# 02_M283.net
KiCad netlist of a schematic drawn in Altium Designer
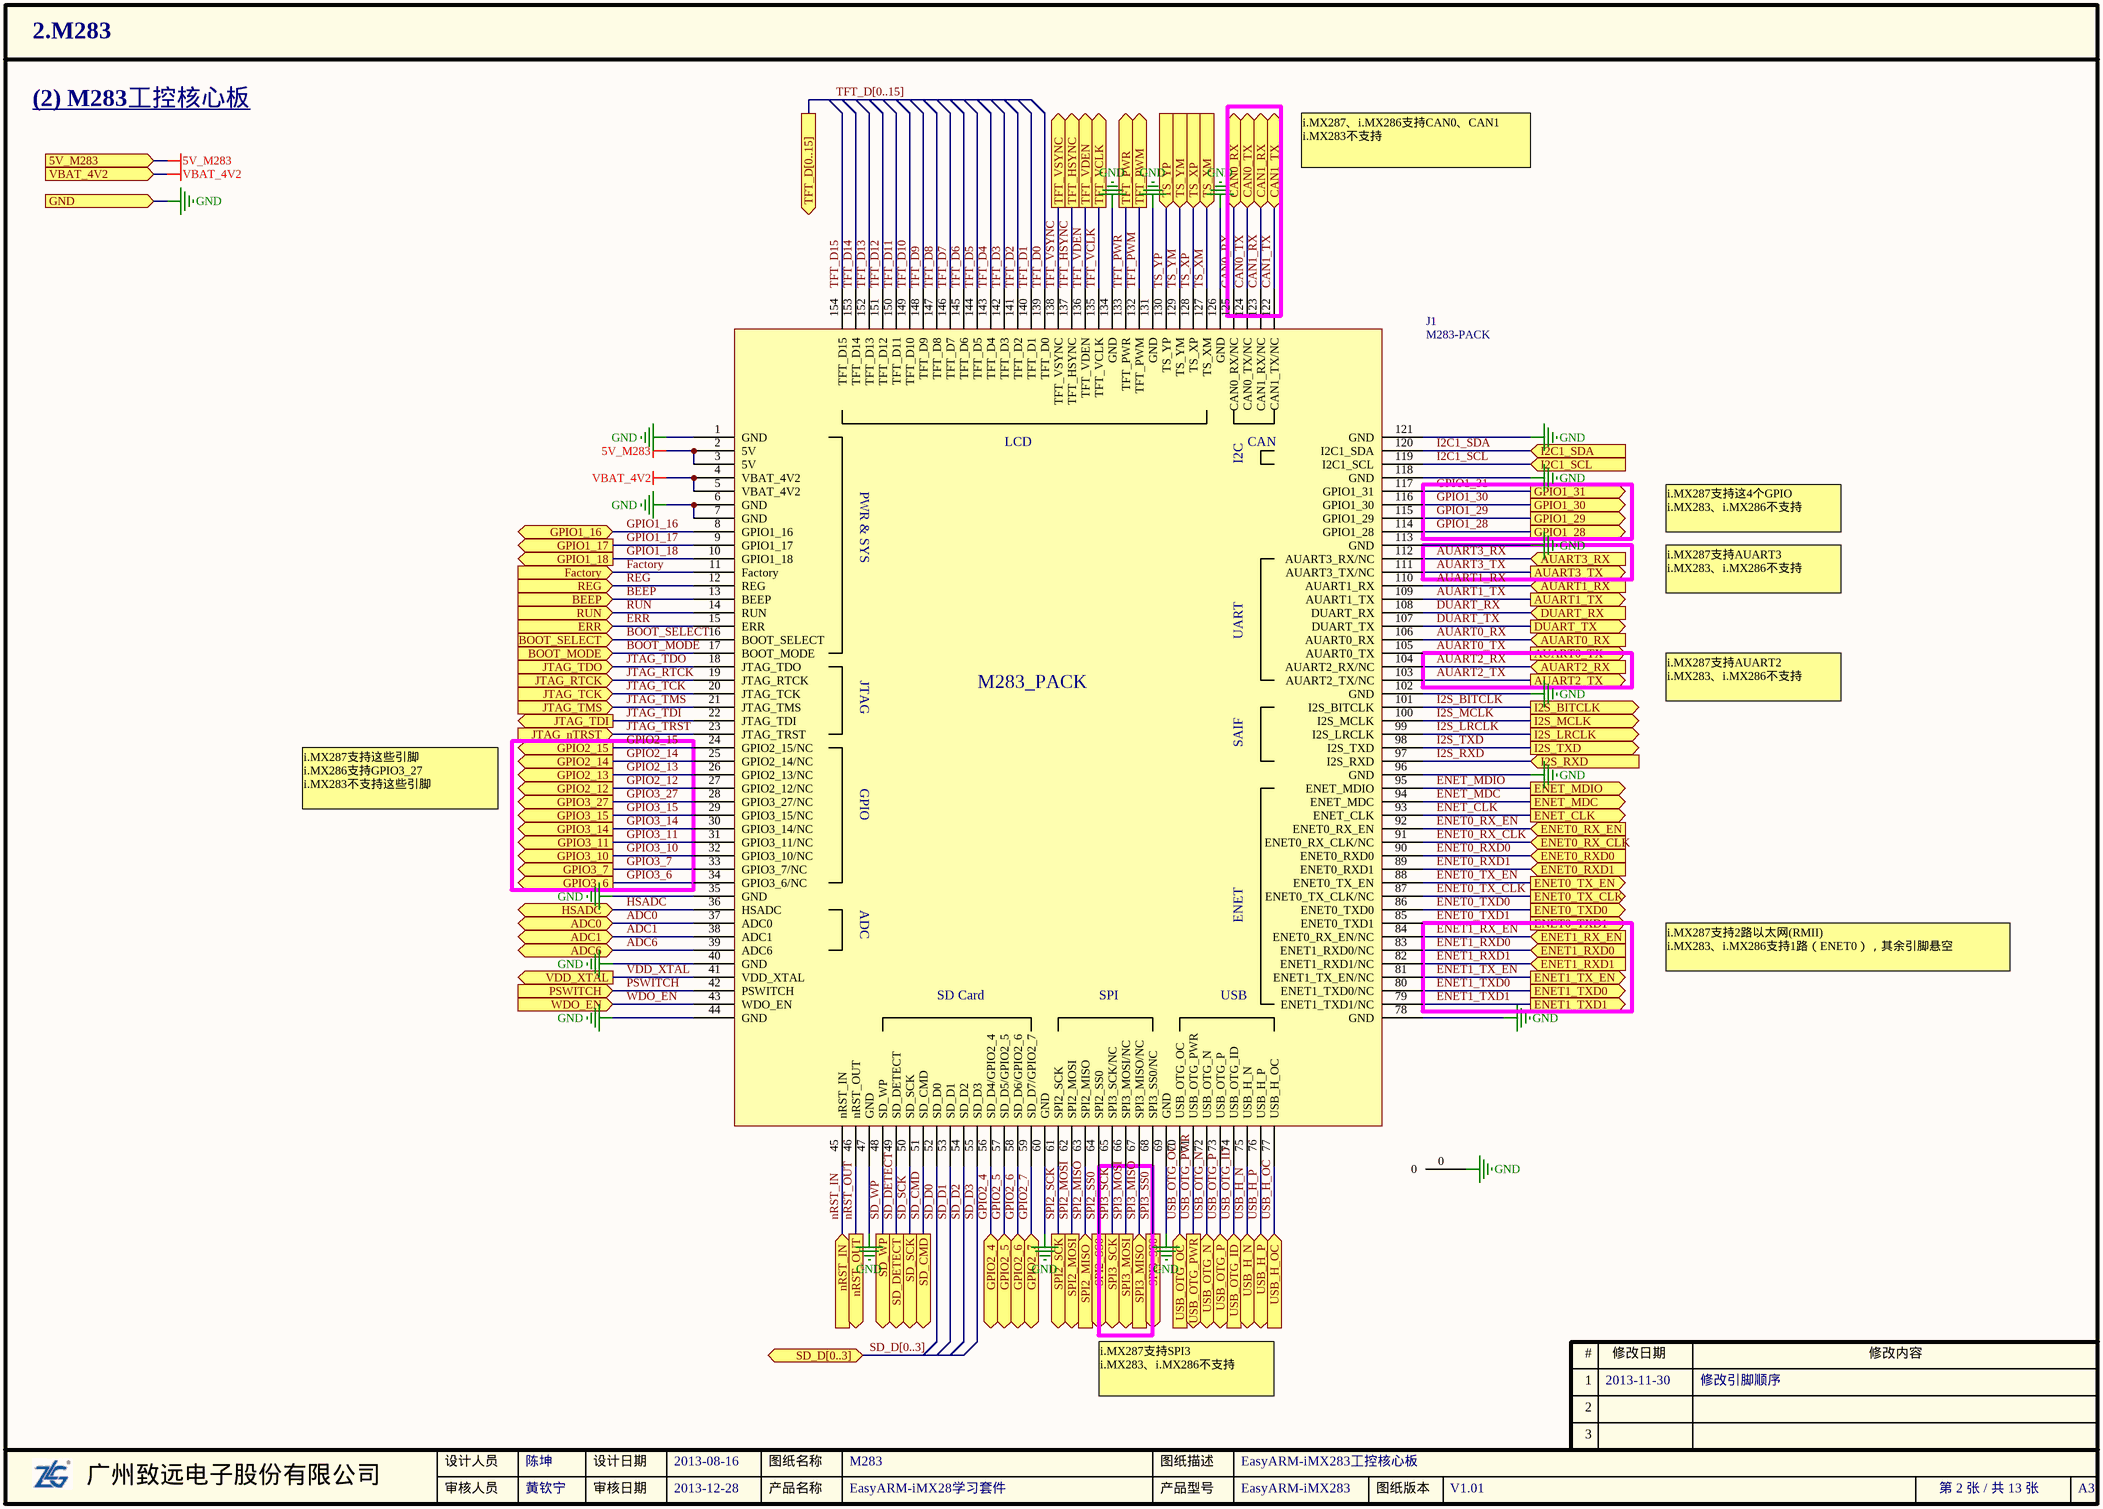
[diagram p0: 02. M283.SchDoc]

(export (version "E")
  (design (tool "Eeschema 10.0.6"))
  (components
    (comp (ref "J1")
      (value "M283-PACK")
      (footprint "M283-154")
      (description "M283")
      (libsource (lib "M283") (part "M283-PACK"))
    )
  )
  (nets
    (net (code "1") (name "/ADC0") (class "Default")
      (node (ref "J1") (pin "37") (pinfunction "ADC0_37") (pintype "passive"))
    )
    (net (code "2") (name "/ADC1") (class "Default")
      (node (ref "J1") (pin "38") (pinfunction "ADC1_38") (pintype "passive"))
    )
    (net (code "3") (name "/ADC6") (class "Default")
      (node (ref "J1") (pin "39") (pinfunction "ADC6_39") (pintype "passive"))
    )
    (net (code "4") (name "/AUART0_RX") (class "Default")
      (node (ref "J1") (pin "106") (pinfunction "AUART0_RX_106") (pintype "passive"))
    )
    (net (code "5") (name "/AUART0_TX") (class "Default")
      (node (ref "J1") (pin "105") (pinfunction "AUART0_TX_105") (pintype "passive"))
    )
    (net (code "6") (name "/AUART1_RX") (class "Default")
      (node (ref "J1") (pin "110") (pinfunction "AUART1_RX_110") (pintype "passive"))
    )
    (net (code "7") (name "/AUART1_TX") (class "Default")
      (node (ref "J1") (pin "109") (pinfunction "AUART1_TX_109") (pintype "passive"))
    )
    (net (code "8") (name "/AUART2_RX") (class "Default")
      (node (ref "J1") (pin "104") (pinfunction "AUART2_RX/NC_104") (pintype "passive"))
    )
    (net (code "9") (name "/AUART2_TX") (class "Default")
      (node (ref "J1") (pin "103") (pinfunction "AUART2_TX/NC_103") (pintype "passive"))
    )
    (net (code "10") (name "/AUART3_RX") (class "Default")
      (node (ref "J1") (pin "112") (pinfunction "AUART3_RX/NC_112") (pintype "passive"))
    )
    (net (code "11") (name "/AUART3_TX") (class "Default")
      (node (ref "J1") (pin "111") (pinfunction "AUART3_TX/NC_111") (pintype "passive"))
    )
    (net (code "12") (name "/BEEP") (class "Default")
      (node (ref "J1") (pin "13") (pinfunction "BEEP_13") (pintype "passive"))
    )
    (net (code "13") (name "/BOOT_MODE") (class "Default")
      (node (ref "J1") (pin "17") (pinfunction "BOOT_MODE_17") (pintype "passive"))
    )
    (net (code "14") (name "/BOOT_SELECT") (class "Default")
      (node (ref "J1") (pin "16") (pinfunction "BOOT_SELECT_16") (pintype "passive"))
    )
    (net (code "15") (name "/CAN0_RX") (class "Default")
      (node (ref "J1") (pin "125") (pinfunction "CAN0_RX/NC_125") (pintype "passive"))
    )
    (net (code "16") (name "/CAN0_TX") (class "Default")
      (node (ref "J1") (pin "124") (pinfunction "CAN0_TX/NC_124") (pintype "passive"))
    )
    (net (code "17") (name "/CAN1_RX") (class "Default")
      (node (ref "J1") (pin "123") (pinfunction "CAN1_RX/NC_123") (pintype "passive"))
    )
    (net (code "18") (name "/CAN1_TX") (class "Default")
      (node (ref "J1") (pin "122") (pinfunction "CAN1_TX/NC_122") (pintype "passive"))
    )
    (net (code "19") (name "/DUART_RX") (class "Default")
      (node (ref "J1") (pin "108") (pinfunction "DUART_RX_108") (pintype "passive"))
    )
    (net (code "20") (name "/DUART_TX") (class "Default")
      (node (ref "J1") (pin "107") (pinfunction "DUART_TX_107") (pintype "passive"))
    )
    (net (code "21") (name "/ENET0_RXD0") (class "Default")
      (node (ref "J1") (pin "90") (pinfunction "ENET0_RXD0_90") (pintype "passive"))
    )
    (net (code "22") (name "/ENET0_RXD1") (class "Default")
      (node (ref "J1") (pin "89") (pinfunction "ENET0_RXD1_89") (pintype "passive"))
    )
    (net (code "23") (name "/ENET0_RX_CLK") (class "Default")
      (node (ref "J1") (pin "91") (pinfunction "ENET0_RX_CLK/NC_91") (pintype "passive"))
    )
    (net (code "24") (name "/ENET0_RX_EN") (class "Default")
      (node (ref "J1") (pin "92") (pinfunction "ENET0_RX_EN_92") (pintype "passive"))
    )
    (net (code "25") (name "/ENET0_TXD0") (class "Default")
      (node (ref "J1") (pin "86") (pinfunction "ENET0_TXD0_86") (pintype "passive"))
    )
    (net (code "26") (name "/ENET0_TXD1") (class "Default")
      (node (ref "J1") (pin "85") (pinfunction "ENET0_TXD1_85") (pintype "passive"))
    )
    (net (code "27") (name "/ENET0_TX_CLK") (class "Default")
      (node (ref "J1") (pin "87") (pinfunction "ENET0_TX_CLK/NC_87") (pintype "passive"))
    )
    (net (code "28") (name "/ENET0_TX_EN") (class "Default")
      (node (ref "J1") (pin "88") (pinfunction "ENET0_TX_EN_88") (pintype "passive"))
    )
    (net (code "29") (name "/ENET1_RXD0") (class "Default")
      (node (ref "J1") (pin "83") (pinfunction "ENET1_RXD0/NC_83") (pintype "passive"))
    )
    (net (code "30") (name "/ENET1_RXD1") (class "Default")
      (node (ref "J1") (pin "82") (pinfunction "ENET1_RXD1/NC_82") (pintype "passive"))
    )
    (net (code "31") (name "/ENET1_RX_EN") (class "Default")
      (node (ref "J1") (pin "84") (pinfunction "ENET0_RX_EN/NC_84") (pintype "passive"))
    )
    (net (code "32") (name "/ENET1_TXD0") (class "Default")
      (node (ref "J1") (pin "80") (pinfunction "ENET1_TXD0/NC_80") (pintype "passive"))
    )
    (net (code "33") (name "/ENET1_TXD1") (class "Default")
      (node (ref "J1") (pin "79") (pinfunction "ENET1_TXD1/NC_79") (pintype "passive"))
    )
    (net (code "34") (name "/ENET1_TX_EN") (class "Default")
      (node (ref "J1") (pin "81") (pinfunction "ENET1_TX_EN/NC_81") (pintype "passive"))
    )
    (net (code "35") (name "/ENET_CLK") (class "Default")
      (node (ref "J1") (pin "93") (pinfunction "ENET_CLK_93") (pintype "passive"))
    )
    (net (code "36") (name "/ENET_MDC") (class "Default")
      (node (ref "J1") (pin "94") (pinfunction "ENET_MDC_94") (pintype "passive"))
    )
    (net (code "37") (name "/ENET_MDIO") (class "Default")
      (node (ref "J1") (pin "95") (pinfunction "ENET_MDIO_95") (pintype "passive"))
    )
    (net (code "38") (name "/ERR") (class "Default")
      (node (ref "J1") (pin "15") (pinfunction "ERR_15") (pintype "passive"))
    )
    (net (code "39") (name "/Factory") (class "Default")
      (node (ref "J1") (pin "11") (pinfunction "Factory_11") (pintype "passive"))
    )
    (net (code "40") (name "/GPIO1_16") (class "Default")
      (node (ref "J1") (pin "8") (pinfunction "GPIO1_16_8") (pintype "passive"))
    )
    (net (code "41") (name "/GPIO1_17") (class "Default")
      (node (ref "J1") (pin "9") (pinfunction "GPIO1_17_9") (pintype "passive"))
    )
    (net (code "42") (name "/GPIO1_18") (class "Default")
      (node (ref "J1") (pin "10") (pinfunction "GPIO1_18_10") (pintype "passive"))
    )
    (net (code "43") (name "/GPIO1_28") (class "Default")
      (node (ref "J1") (pin "114") (pinfunction "GPIO1_28_114") (pintype "passive"))
    )
    (net (code "44") (name "/GPIO1_29") (class "Default")
      (node (ref "J1") (pin "115") (pinfunction "GPIO1_29_115") (pintype "passive"))
    )
    (net (code "45") (name "/GPIO1_30") (class "Default")
      (node (ref "J1") (pin "116") (pinfunction "GPIO1_30_116") (pintype "passive"))
    )
    (net (code "46") (name "/GPIO1_31") (class "Default")
      (node (ref "J1") (pin "117") (pinfunction "GPIO1_31_117") (pintype "passive"))
    )
    (net (code "47") (name "/GPIO2_4") (class "Default")
      (node (ref "J1") (pin "56") (pinfunction "SD_D4/GPIO2_4_56") (pintype "passive"))
    )
    (net (code "48") (name "/GPIO2_5") (class "Default")
      (node (ref "J1") (pin "57") (pinfunction "SD_D5/GPIO2_5_57") (pintype "passive"))
    )
    (net (code "49") (name "/GPIO2_6") (class "Default")
      (node (ref "J1") (pin "58") (pinfunction "SD_D6/GPIO2_6_58") (pintype "passive"))
    )
    (net (code "50") (name "/GPIO2_7") (class "Default")
      (node (ref "J1") (pin "59") (pinfunction "SD_D7/GPIO2_7_59") (pintype "passive"))
    )
    (net (code "51") (name "/GPIO2_12") (class "Default")
      (node (ref "J1") (pin "27") (pinfunction "GPIO2_12/NC_27") (pintype "passive"))
    )
    (net (code "52") (name "/GPIO2_13") (class "Default")
      (node (ref "J1") (pin "26") (pinfunction "GPIO2_13/NC_26") (pintype "passive"))
    )
    (net (code "53") (name "/GPIO2_14") (class "Default")
      (node (ref "J1") (pin "25") (pinfunction "GPIO2_14/NC_25") (pintype "passive"))
    )
    (net (code "54") (name "/GPIO2_15") (class "Default")
      (node (ref "J1") (pin "24") (pinfunction "GPIO2_15/NC_24") (pintype "passive"))
    )
    (net (code "55") (name "/GPIO3_6") (class "Default")
      (node (ref "J1") (pin "34") (pinfunction "GPIO3_6/NC_34") (pintype "passive"))
    )
    (net (code "56") (name "/GPIO3_7") (class "Default")
      (node (ref "J1") (pin "33") (pinfunction "GPIO3_7/NC_33") (pintype "passive"))
    )
    (net (code "57") (name "/GPIO3_10") (class "Default")
      (node (ref "J1") (pin "32") (pinfunction "GPIO3_10/NC_32") (pintype "passive"))
    )
    (net (code "58") (name "/GPIO3_11") (class "Default")
      (node (ref "J1") (pin "31") (pinfunction "GPIO3_11/NC_31") (pintype "passive"))
    )
    (net (code "59") (name "/GPIO3_14") (class "Default")
      (node (ref "J1") (pin "30") (pinfunction "GPIO3_14/NC_30") (pintype "passive"))
    )
    (net (code "60") (name "/GPIO3_15") (class "Default")
      (node (ref "J1") (pin "29") (pinfunction "GPIO3_15/NC_29") (pintype "passive"))
    )
    (net (code "61") (name "/GPIO3_27") (class "Default")
      (node (ref "J1") (pin "28") (pinfunction "GPIO3_27/NC_28") (pintype "passive"))
    )
    (net (code "62") (name "/HSADC") (class "Default")
      (node (ref "J1") (pin "36") (pinfunction "HSADC_36") (pintype "passive"))
    )
    (net (code "63") (name "/I2C1_SCL") (class "Default")
      (node (ref "J1") (pin "119") (pinfunction "I2C1_SCL_119") (pintype "passive"))
    )
    (net (code "64") (name "/I2C1_SDA") (class "Default")
      (node (ref "J1") (pin "120") (pinfunction "I2C1_SDA_120") (pintype "passive"))
    )
    (net (code "65") (name "/I2S_BITCLK") (class "Default")
      (node (ref "J1") (pin "101") (pinfunction "I2S_BITCLK_101") (pintype "passive"))
    )
    (net (code "66") (name "/I2S_LRCLK") (class "Default")
      (node (ref "J1") (pin "99") (pinfunction "I2S_LRCLK_99") (pintype "passive"))
    )
    (net (code "67") (name "/I2S_MCLK") (class "Default")
      (node (ref "J1") (pin "100") (pinfunction "I2S_MCLK_100") (pintype "passive"))
    )
    (net (code "68") (name "/I2S_RXD") (class "Default")
      (node (ref "J1") (pin "97") (pinfunction "I2S_RXD_97") (pintype "passive"))
    )
    (net (code "69") (name "/I2S_TXD") (class "Default")
      (node (ref "J1") (pin "98") (pinfunction "I2S_TXD_98") (pintype "passive"))
    )
    (net (code "70") (name "/JTAG_RTCK") (class "Default")
      (node (ref "J1") (pin "19") (pinfunction "JTAG_RTCK_19") (pintype "passive"))
    )
    (net (code "71") (name "/JTAG_TCK") (class "Default")
      (node (ref "J1") (pin "20") (pinfunction "JTAG_TCK_20") (pintype "passive"))
    )
    (net (code "72") (name "/JTAG_TDI") (class "Default")
      (node (ref "J1") (pin "22") (pinfunction "JTAG_TDI_22") (pintype "passive"))
    )
    (net (code "73") (name "/JTAG_TDO") (class "Default")
      (node (ref "J1") (pin "18") (pinfunction "JTAG_TDO_18") (pintype "passive"))
    )
    (net (code "74") (name "/JTAG_TMS") (class "Default")
      (node (ref "J1") (pin "21") (pinfunction "JTAG_TMS_21") (pintype "passive"))
    )
    (net (code "75") (name "/JTAG_TRST") (class "Default")
      (node (ref "J1") (pin "23") (pinfunction "JTAG_TRST_23") (pintype "passive"))
    )
    (net (code "76") (name "/PSWITCH") (class "Default")
      (node (ref "J1") (pin "42") (pinfunction "PSWITCH_42") (pintype "passive"))
    )
    (net (code "77") (name "/REG") (class "Default")
      (node (ref "J1") (pin "12") (pinfunction "REG_12") (pintype "passive"))
    )
    (net (code "78") (name "/RUN") (class "Default")
      (node (ref "J1") (pin "14") (pinfunction "RUN_14") (pintype "passive"))
    )
    (net (code "79") (name "/SD_CMD") (class "Default")
      (node (ref "J1") (pin "51") (pinfunction "SD_CMD_51") (pintype "passive"))
    )
    (net (code "80") (name "/SD_D0") (class "Default")
      (node (ref "J1") (pin "52") (pinfunction "SD_D0_52") (pintype "passive"))
    )
    (net (code "81") (name "/SD_D1") (class "Default")
      (node (ref "J1") (pin "53") (pinfunction "SD_D1_53") (pintype "passive"))
    )
    (net (code "82") (name "/SD_D2") (class "Default")
      (node (ref "J1") (pin "54") (pinfunction "SD_D2_54") (pintype "passive"))
    )
    (net (code "83") (name "/SD_D3") (class "Default")
      (node (ref "J1") (pin "55") (pinfunction "SD_D3_55") (pintype "passive"))
    )
    (net (code "84") (name "/SD_DETECT") (class "Default")
      (node (ref "J1") (pin "49") (pinfunction "SD_DETECT_49") (pintype "passive"))
    )
    (net (code "86") (name "/SD_SCK") (class "Default")
      (node (ref "J1") (pin "50") (pinfunction "SD_SCK_50") (pintype "passive"))
    )
    (net (code "87") (name "/SD_WP") (class "Default")
      (node (ref "J1") (pin "48") (pinfunction "SD_WP_48") (pintype "passive"))
    )
    (net (code "88") (name "/SPI2_MISO") (class "Default")
      (node (ref "J1") (pin "63") (pinfunction "SPI2_MISO_63") (pintype "passive"))
    )
    (net (code "89") (name "/SPI2_MOSI") (class "Default")
      (node (ref "J1") (pin "62") (pinfunction "SPI2_MOSI_62") (pintype "passive"))
    )
    (net (code "90") (name "/SPI2_SCK") (class "Default")
      (node (ref "J1") (pin "61") (pinfunction "SPI2_SCK_61") (pintype "passive"))
    )
    (net (code "91") (name "/SPI2_SS0") (class "Default")
      (node (ref "J1") (pin "64") (pinfunction "SPI2_SS0_64") (pintype "passive"))
    )
    (net (code "92") (name "/SPI3_MISO") (class "Default")
      (node (ref "J1") (pin "67") (pinfunction "SPI3_MISO/NC_67") (pintype "passive"))
    )
    (net (code "93") (name "/SPI3_MOSI") (class "Default")
      (node (ref "J1") (pin "66") (pinfunction "SPI3_MOSI/NC_66") (pintype "passive"))
    )
    (net (code "94") (name "/SPI3_SCK") (class "Default")
      (node (ref "J1") (pin "65") (pinfunction "SPI3_SCK/NC_65") (pintype "passive"))
    )
    (net (code "95") (name "/SPI3_SS0") (class "Default")
      (node (ref "J1") (pin "68") (pinfunction "SPI3_SS0/NC_68") (pintype "passive"))
    )
    (net (code "96") (name "/TFT_D0") (class "Default")
      (node (ref "J1") (pin "139") (pinfunction "TFT_D0_139") (pintype "passive"))
    )
    (net (code "97") (name "/TFT_D1") (class "Default")
      (node (ref "J1") (pin "140") (pinfunction "TFT_D1_140") (pintype "passive"))
    )
    (net (code "98") (name "/TFT_D2") (class "Default")
      (node (ref "J1") (pin "141") (pinfunction "TFT_D2_141") (pintype "passive"))
    )
    (net (code "99") (name "/TFT_D3") (class "Default")
      (node (ref "J1") (pin "142") (pinfunction "TFT_D3_142") (pintype "passive"))
    )
    (net (code "100") (name "/TFT_D4") (class "Default")
      (node (ref "J1") (pin "143") (pinfunction "TFT_D4_143") (pintype "passive"))
    )
    (net (code "101") (name "/TFT_D5") (class "Default")
      (node (ref "J1") (pin "144") (pinfunction "TFT_D5_144") (pintype "passive"))
    )
    (net (code "102") (name "/TFT_D6") (class "Default")
      (node (ref "J1") (pin "145") (pinfunction "TFT_D6_145") (pintype "passive"))
    )
    (net (code "103") (name "/TFT_D7") (class "Default")
      (node (ref "J1") (pin "146") (pinfunction "TFT_D7_146") (pintype "passive"))
    )
    (net (code "104") (name "/TFT_D8") (class "Default")
      (node (ref "J1") (pin "147") (pinfunction "TFT_D8_147") (pintype "passive"))
    )
    (net (code "105") (name "/TFT_D9") (class "Default")
      (node (ref "J1") (pin "148") (pinfunction "TFT_D9_148") (pintype "passive"))
    )
    (net (code "106") (name "/TFT_D10") (class "Default")
      (node (ref "J1") (pin "149") (pinfunction "TFT_D10_149") (pintype "passive"))
    )
    (net (code "107") (name "/TFT_D11") (class "Default")
      (node (ref "J1") (pin "150") (pinfunction "TFT_D11_150") (pintype "passive"))
    )
    (net (code "108") (name "/TFT_D12") (class "Default")
      (node (ref "J1") (pin "151") (pinfunction "TFT_D12_151") (pintype "passive"))
    )
    (net (code "109") (name "/TFT_D13") (class "Default")
      (node (ref "J1") (pin "152") (pinfunction "TFT_D13_152") (pintype "passive"))
    )
    (net (code "110") (name "/TFT_D14") (class "Default")
      (node (ref "J1") (pin "153") (pinfunction "TFT_D14_153") (pintype "passive"))
    )
    (net (code "111") (name "/TFT_D15") (class "Default")
      (node (ref "J1") (pin "154") (pinfunction "TFT_D15_154") (pintype "passive"))
    )
    (net (code "113") (name "/TFT_HSYNC") (class "Default")
      (node (ref "J1") (pin "137") (pinfunction "TFT_HSYNC_137") (pintype "passive"))
    )
    (net (code "114") (name "/TFT_PWM") (class "Default")
      (node (ref "J1") (pin "132") (pinfunction "TFT_PWM_132") (pintype "passive"))
    )
    (net (code "115") (name "/TFT_PWR") (class "Default")
      (node (ref "J1") (pin "133") (pinfunction "TFT_PWR_133") (pintype "passive"))
    )
    (net (code "116") (name "/TFT_VCLK") (class "Default")
      (node (ref "J1") (pin "135") (pinfunction "TFT_VCLK_135") (pintype "passive"))
    )
    (net (code "117") (name "/TFT_VDEN") (class "Default")
      (node (ref "J1") (pin "136") (pinfunction "TFT_VDEN_136") (pintype "passive"))
    )
    (net (code "118") (name "/TFT_VSYNC") (class "Default")
      (node (ref "J1") (pin "138") (pinfunction "TFT_VSYNC_138") (pintype "passive"))
    )
    (net (code "119") (name "/TS_XM") (class "Default")
      (node (ref "J1") (pin "127") (pinfunction "TS_XM_127") (pintype "passive"))
    )
    (net (code "120") (name "/TS_XP") (class "Default")
      (node (ref "J1") (pin "128") (pinfunction "TS_XP_128") (pintype "passive"))
    )
    (net (code "121") (name "/TS_YM") (class "Default")
      (node (ref "J1") (pin "129") (pinfunction "TS_YM_129") (pintype "passive"))
    )
    (net (code "122") (name "/TS_YP") (class "Default")
      (node (ref "J1") (pin "130") (pinfunction "TS_YP_130") (pintype "passive"))
    )
    (net (code "123") (name "/USB_H_N") (class "Default")
      (node (ref "J1") (pin "75") (pinfunction "USB_H_N_75") (pintype "passive"))
    )
    (net (code "124") (name "/USB_H_OC") (class "Default")
      (node (ref "J1") (pin "77") (pinfunction "USB_H_OC_77") (pintype "passive"))
    )
    (net (code "125") (name "/USB_H_P") (class "Default")
      (node (ref "J1") (pin "76") (pinfunction "USB_H_P_76") (pintype "passive"))
    )
    (net (code "126") (name "/USB_OTG_ID") (class "Default")
      (node (ref "J1") (pin "74") (pinfunction "USB_OTG_ID_74") (pintype "passive"))
    )
    (net (code "127") (name "/USB_OTG_N") (class "Default")
      (node (ref "J1") (pin "72") (pinfunction "USB_OTG_N_72") (pintype "passive"))
    )
    (net (code "128") (name "/USB_OTG_OC") (class "Default")
      (node (ref "J1") (pin "70") (pinfunction "USB_OTG_OC_70") (pintype "passive"))
    )
    (net (code "129") (name "/USB_OTG_P") (class "Default")
      (node (ref "J1") (pin "73") (pinfunction "USB_OTG_P_73") (pintype "passive"))
    )
    (net (code "130") (name "/USB_OTG_PWR") (class "Default")
      (node (ref "J1") (pin "71") (pinfunction "USB_OTG_PWR_71") (pintype "passive"))
    )
    (net (code "131") (name "/VDD_XTAL") (class "Default")
      (node (ref "J1") (pin "41") (pinfunction "VDD_XTAL_41") (pintype "passive"))
    )
    (net (code "132") (name "/WDO_EN") (class "Default")
      (node (ref "J1") (pin "43") (pinfunction "WDO_EN_43") (pintype "passive"))
    )
    (net (code "133") (name "/nRST_IN") (class "Default")
      (node (ref "J1") (pin "45") (pinfunction "nRST_IN_45") (pintype "passive"))
    )
    (net (code "134") (name "/nRST_OUT") (class "Default")
      (node (ref "J1") (pin "46") (pinfunction "nRST_OUT_46") (pintype "passive"))
    )
    (net (code "135") (name "5V_M283") (class "Default")
      (node (ref "J1") (pin "2") (pinfunction "5V_2") (pintype "passive"))
      (node (ref "J1") (pin "3") (pinfunction "5V_3") (pintype "passive"))
    )
    (net (code "136") (name "GND") (class "Default")
      (node (ref "J1") (pin "0") (pinfunction "0_0") (pintype "passive"))
      (node (ref "J1") (pin "1") (pinfunction "GND_1") (pintype "passive"))
      (node (ref "J1") (pin "102") (pinfunction "GND_102") (pintype "passive"))
      (node (ref "J1") (pin "113") (pinfunction "GND_113") (pintype "passive"))
      (node (ref "J1") (pin "118") (pinfunction "GND_118") (pintype "passive"))
      (node (ref "J1") (pin "121") (pinfunction "GND_121") (pintype "passive"))
      (node (ref "J1") (pin "126") (pinfunction "GND_126") (pintype "passive"))
      (node (ref "J1") (pin "131") (pinfunction "GND_131") (pintype "passive"))
      (node (ref "J1") (pin "134") (pinfunction "GND_134") (pintype "passive"))
      (node (ref "J1") (pin "35") (pinfunction "GND_35") (pintype "passive"))
      (node (ref "J1") (pin "40") (pinfunction "GND_40") (pintype "passive"))
      (node (ref "J1") (pin "44") (pinfunction "GND_44") (pintype "passive"))
      (node (ref "J1") (pin "47") (pinfunction "GND_47") (pintype "passive"))
      (node (ref "J1") (pin "6") (pinfunction "GND_6") (pintype "passive"))
      (node (ref "J1") (pin "60") (pinfunction "GND_60") (pintype "passive"))
      (node (ref "J1") (pin "69") (pinfunction "GND_69") (pintype "passive"))
      (node (ref "J1") (pin "7") (pinfunction "GND_7") (pintype "passive"))
      (node (ref "J1") (pin "78") (pinfunction "GND_78") (pintype "passive"))
      (node (ref "J1") (pin "96") (pinfunction "GND_96") (pintype "passive"))
    )
    (net (code "137") (name "VBAT_4V2") (class "Default")
      (node (ref "J1") (pin "4") (pinfunction "VBAT_4V2_4") (pintype "passive"))
      (node (ref "J1") (pin "5") (pinfunction "VBAT_4V2_5") (pintype "passive"))
    )
  )
)
